# rcswitch.net
KiCad netlist of a schematic drawn in EAGLE
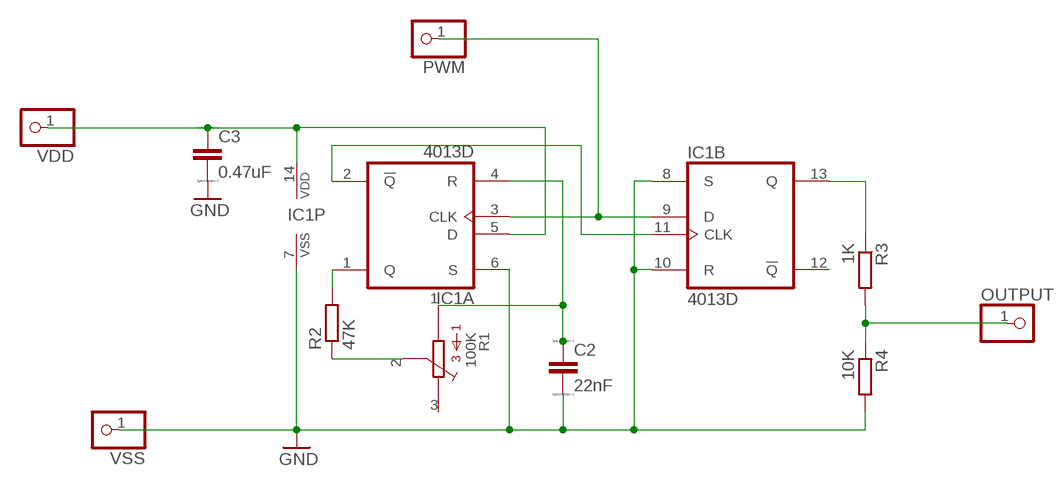
[diagram p0: schematic, sheet 1]

(export (version "E")
  (design (tool "Eeschema 10.0.6"))
  (components
    (comp (ref "C2")
      (value "22nF")
      (footprint "eagle-import:C3216")
      (libsource (lib "eagle-import") (part "CC3216"))
    )
    (comp (ref "C3")
      (value "0.47uF")
      (footprint "eagle-import:C3216")
      (libsource (lib "eagle-import") (part "CC3216"))
    )
    (comp (ref "IC1")
      (value "4013D")
      (footprint "eagle-import:SO14")
      (libsource (lib "eagle-import") (part "4013D"))
    )
    (comp (ref "OUTPUT")
      (value "PINHD-1X1")
      (footprint "eagle-import:1X01")
      (libsource (lib "eagle-import") (part "PINHD-1X1"))
    )
    (comp (ref "PWM")
      (value "PINHD-1X1")
      (footprint "eagle-import:1X01")
      (libsource (lib "eagle-import") (part "PINHD-1X1"))
    )
    (comp (ref "R1")
      (value "100K")
      (footprint "eagle-import:3386-MULTI")
      (libsource (lib "eagle-import") (part "3386"))
    )
    (comp (ref "R2")
      (value "47K")
      (footprint "eagle-import:R3225")
      (libsource (lib "eagle-import") (part "R-EU_R3225"))
    )
    (comp (ref "R3")
      (value "1K")
      (footprint "eagle-import:R3225")
      (libsource (lib "eagle-import") (part "R-EU_R3225"))
    )
    (comp (ref "R4")
      (value "10K")
      (footprint "eagle-import:R3225")
      (libsource (lib "eagle-import") (part "R-EU_R3225"))
    )
    (comp (ref "VDD")
      (value "PINHD-1X1")
      (footprint "eagle-import:1X01")
      (libsource (lib "eagle-import") (part "PINHD-1X1"))
    )
    (comp (ref "VSS")
      (value "PINHD-1X1")
      (footprint "eagle-import:1X01")
      (libsource (lib "eagle-import") (part "PINHD-1X1"))
    )
  )
  (nets
    (net (code "1") (name "GND") (class "Default")
      (node (ref "C2") (pin "2") (pinfunction "2_2") (pintype "passive"))
      (node (ref "C3") (pin "2") (pinfunction "2_2") (pintype "passive"))
      (node (ref "IC1") (pin "10") (pinfunction "R_10") (pintype "input"))
      (node (ref "IC1") (pin "6") (pinfunction "S_6") (pintype "input"))
      (node (ref "IC1") (pin "7") (pinfunction "VSS_7") (pintype "power_in"))
      (node (ref "IC1") (pin "8") (pinfunction "S_8") (pintype "input"))
      (node (ref "R4") (pin "2") (pinfunction "2_2") (pintype "passive"))
      (node (ref "VSS") (pin "1") (pinfunction "1_1") (pintype "passive"))
    )
    (net (code "2") (name "Net-(IC1A-CLK)") (class "Default")
      (node (ref "IC1") (pin "3") (pinfunction "CLK_3") (pintype "input"))
      (node (ref "IC1") (pin "9") (pinfunction "D_9") (pintype "input"))
      (node (ref "PWM") (pin "1") (pinfunction "1_1") (pintype "passive"))
    )
    (net (code "3") (name "Net-(IC1A-D)") (class "Default")
      (node (ref "C3") (pin "1") (pinfunction "1_1") (pintype "passive"))
      (node (ref "IC1") (pin "14") (pinfunction "VDD_14") (pintype "power_in"))
      (node (ref "IC1") (pin "5") (pinfunction "D_5") (pintype "input"))
      (node (ref "VDD") (pin "1") (pinfunction "1_1") (pintype "passive"))
    )
    (net (code "4") (name "Net-(IC1A-Q)") (class "Default")
      (node (ref "IC1") (pin "1") (pinfunction "Q_1") (pintype "output"))
      (node (ref "R2") (pin "2") (pinfunction "2_2") (pintype "passive"))
    )
    (net (code "5") (name "Net-(IC1A-R)") (class "Default")
      (node (ref "C2") (pin "1") (pinfunction "1_1") (pintype "passive"))
      (node (ref "IC1") (pin "4") (pinfunction "R_4") (pintype "input"))
      (node (ref "R1") (pin "1") (pinfunction "1_1") (pintype "passive"))
    )
    (net (code "6") (name "Net-(IC1A-~{Q})") (class "Default")
      (node (ref "IC1") (pin "11") (pinfunction "CLK_11") (pintype "input"))
      (node (ref "IC1") (pin "2") (pinfunction "~{Q}_2") (pintype "output"))
    )
    (net (code "7") (name "Net-(IC1B-Q)") (class "Default")
      (node (ref "IC1") (pin "13") (pinfunction "Q_13") (pintype "output"))
      (node (ref "R3") (pin "1") (pinfunction "1_1") (pintype "passive"))
    )
    (net (code "8") (name "Net-(OUTPUT-Pad1)") (class "Default")
      (node (ref "OUTPUT") (pin "1") (pinfunction "1_1") (pintype "passive"))
      (node (ref "R3") (pin "2") (pinfunction "2_2") (pintype "passive"))
      (node (ref "R4") (pin "1") (pinfunction "1_1") (pintype "passive"))
    )
    (net (code "9") (name "Net-(R1-Pad2)") (class "Default")
      (node (ref "R1") (pin "2") (pinfunction "2_2") (pintype "passive"))
      (node (ref "R2") (pin "1") (pinfunction "1_1") (pintype "passive"))
    )
    (net (code "10") (name "unconnected-(IC1B-~{Q}-Pad12)") (class "Default")
      (node (ref "IC1") (pin "12") (pinfunction "~{Q}_12") (pintype "output"))
    )
    (net (code "11") (name "unconnected-(R1-Pad3)") (class "Default")
      (node (ref "R1") (pin "3") (pinfunction "3_3") (pintype "passive"))
    )
    (net (code "12") (name "unconnected-(R1-Pad4)") (class "Default")
      (node (ref "R1") (pin "4") (pinfunction "4_4") (pintype "passive"))
    )
    (net (code "13") (name "unconnected-(R1-Pad5)") (class "Default")
      (node (ref "R1") (pin "5") (pinfunction "5_5") (pintype "passive"))
    )
    (net (code "14") (name "unconnected-(R1-Pad6)") (class "Default")
      (node (ref "R1") (pin "6") (pinfunction "6_6") (pintype "passive"))
    )
  )
)
